# do1.net
KiCad netlist of a schematic drawn in Altium Designer
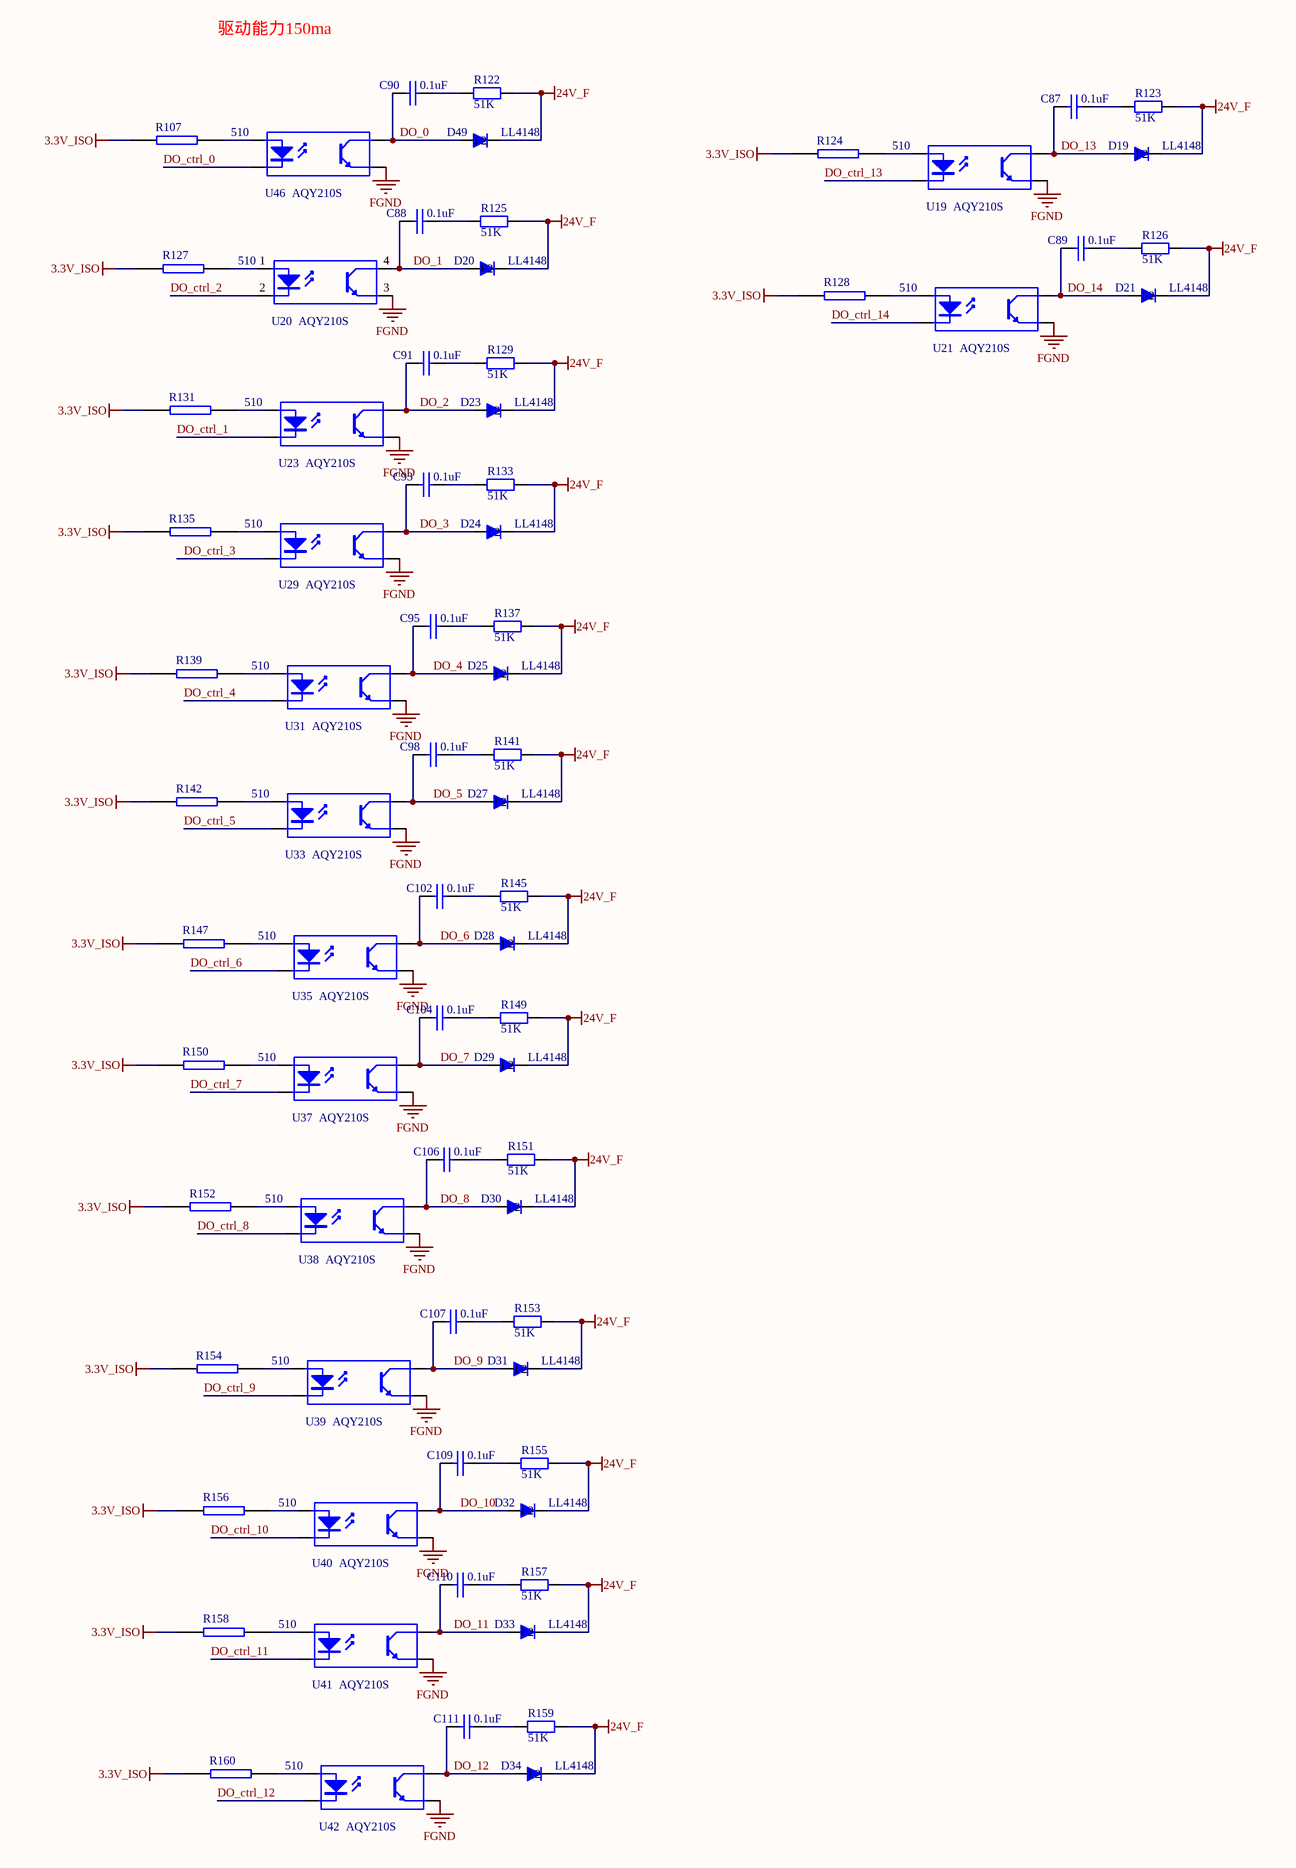
[diagram p0: do1.SchDoc]

(export (version "E")
  (design (tool "Eeschema 10.0.6"))
  (components
    (comp (ref "C87")
      (value "0.1uF")
      (footprint "0603C")
      (description "Capacitor")
      (libsource (lib "*") (part "CAP"))
    )
    (comp (ref "C88")
      (value "0.1uF")
      (footprint "0603C")
      (description "Capacitor")
      (libsource (lib "*") (part "CAP"))
    )
    (comp (ref "C89")
      (value "0.1uF")
      (footprint "0603C")
      (description "Capacitor")
      (libsource (lib "*") (part "CAP"))
    )
    (comp (ref "C90")
      (value "0.1uF")
      (footprint "0603C")
      (description "Capacitor")
      (libsource (lib "*") (part "CAP"))
    )
    (comp (ref "C91")
      (value "0.1uF")
      (footprint "0603C")
      (description "Capacitor")
      (libsource (lib "*") (part "CAP"))
    )
    (comp (ref "C93")
      (value "0.1uF")
      (footprint "0603C")
      (description "Capacitor")
      (libsource (lib "*") (part "CAP"))
    )
    (comp (ref "C95")
      (value "0.1uF")
      (footprint "0603C")
      (description "Capacitor")
      (libsource (lib "*") (part "CAP"))
    )
    (comp (ref "C98")
      (value "0.1uF")
      (footprint "0603C")
      (description "Capacitor")
      (libsource (lib "*") (part "CAP"))
    )
    (comp (ref "C102")
      (value "0.1uF")
      (footprint "0603C")
      (description "Capacitor")
      (libsource (lib "*") (part "CAP"))
    )
    (comp (ref "C104")
      (value "0.1uF")
      (footprint "0603C")
      (description "Capacitor")
      (libsource (lib "*") (part "CAP"))
    )
    (comp (ref "C106")
      (value "0.1uF")
      (footprint "0603C")
      (description "Capacitor")
      (libsource (lib "*") (part "CAP"))
    )
    (comp (ref "C107")
      (value "0.1uF")
      (footprint "0603C")
      (description "Capacitor")
      (libsource (lib "*") (part "CAP"))
    )
    (comp (ref "C109")
      (value "0.1uF")
      (footprint "0603C")
      (description "Capacitor")
      (libsource (lib "*") (part "CAP"))
    )
    (comp (ref "C110")
      (value "0.1uF")
      (footprint "0603C")
      (description "Capacitor")
      (libsource (lib "*") (part "CAP"))
    )
    (comp (ref "C111")
      (value "0.1uF")
      (footprint "0603C")
      (description "Capacitor")
      (libsource (lib "*") (part "CAP"))
    )
    (comp (ref "D19")
      (value "LL4148")
      (footprint "DO-213AB/LL34/MiniMELF")
      (description "VISHAY,LL4148,圆柱体MiniMELF100V/2A,ROHS")
      (libsource (lib "Device2018") (part "LL4148"))
    )
    (comp (ref "D20")
      (value "LL4148")
      (footprint "DO-213AB/LL34/MiniMELF")
      (description "VISHAY,LL4148,圆柱体MiniMELF100V/2A,ROHS")
      (libsource (lib "Device2018") (part "LL4148"))
    )
    (comp (ref "D21")
      (value "LL4148")
      (footprint "DO-213AB/LL34/MiniMELF")
      (description "VISHAY,LL4148,圆柱体MiniMELF100V/2A,ROHS")
      (libsource (lib "Device2018") (part "LL4148"))
    )
    (comp (ref "D23")
      (value "LL4148")
      (footprint "DO-213AB/LL34/MiniMELF")
      (description "VISHAY,LL4148,圆柱体MiniMELF100V/2A,ROHS")
      (libsource (lib "Device2018") (part "LL4148"))
    )
    (comp (ref "D24")
      (value "LL4148")
      (footprint "DO-213AB/LL34/MiniMELF")
      (description "VISHAY,LL4148,圆柱体MiniMELF100V/2A,ROHS")
      (libsource (lib "Device2018") (part "LL4148"))
    )
    (comp (ref "D25")
      (value "LL4148")
      (footprint "DO-213AB/LL34/MiniMELF")
      (description "VISHAY,LL4148,圆柱体MiniMELF100V/2A,ROHS")
      (libsource (lib "Device2018") (part "LL4148"))
    )
    (comp (ref "D27")
      (value "LL4148")
      (footprint "DO-213AB/LL34/MiniMELF")
      (description "VISHAY,LL4148,圆柱体MiniMELF100V/2A,ROHS")
      (libsource (lib "Device2018") (part "LL4148"))
    )
    (comp (ref "D28")
      (value "LL4148")
      (footprint "DO-213AB/LL34/MiniMELF")
      (description "VISHAY,LL4148,圆柱体MiniMELF100V/2A,ROHS")
      (libsource (lib "Device2018") (part "LL4148"))
    )
    (comp (ref "D29")
      (value "LL4148")
      (footprint "DO-213AB/LL34/MiniMELF")
      (description "VISHAY,LL4148,圆柱体MiniMELF100V/2A,ROHS")
      (libsource (lib "Device2018") (part "LL4148"))
    )
    (comp (ref "D30")
      (value "LL4148")
      (footprint "DO-213AB/LL34/MiniMELF")
      (description "VISHAY,LL4148,圆柱体MiniMELF100V/2A,ROHS")
      (libsource (lib "Device2018") (part "LL4148"))
    )
    (comp (ref "D31")
      (value "LL4148")
      (footprint "DO-213AB/LL34/MiniMELF")
      (description "VISHAY,LL4148,圆柱体MiniMELF100V/2A,ROHS")
      (libsource (lib "Device2018") (part "LL4148"))
    )
    (comp (ref "D32")
      (value "LL4148")
      (footprint "DO-213AB/LL34/MiniMELF")
      (description "VISHAY,LL4148,圆柱体MiniMELF100V/2A,ROHS")
      (libsource (lib "Device2018") (part "LL4148"))
    )
    (comp (ref "D33")
      (value "LL4148")
      (footprint "DO-213AB/LL34/MiniMELF")
      (description "VISHAY,LL4148,圆柱体MiniMELF100V/2A,ROHS")
      (libsource (lib "Device2018") (part "LL4148"))
    )
    (comp (ref "D34")
      (value "LL4148")
      (footprint "DO-213AB/LL34/MiniMELF")
      (description "VISHAY,LL4148,圆柱体MiniMELF100V/2A,ROHS")
      (libsource (lib "Device2018") (part "LL4148"))
    )
    (comp (ref "D49")
      (value "LL4148")
      (footprint "DO-213AB/LL34/MiniMELF")
      (description "VISHAY,LL4148,圆柱体MiniMELF100V/2A,ROHS")
      (libsource (lib "Device2018") (part "LL4148"))
    )
    (comp (ref "R107") (value "510") (footprint "0603R") (libsource (lib "*") (part "RES2")))
    (comp (ref "R122") (value "51K") (footprint "0603R") (libsource (lib "MQlibrary") (part "Res0805M")))
    (comp (ref "R123") (value "51K") (footprint "0603R") (libsource (lib "MQlibrary") (part "Res0805M")))
    (comp (ref "R124") (value "510") (footprint "0603R") (libsource (lib "*") (part "RES2")))
    (comp (ref "R125") (value "51K") (footprint "0603R") (libsource (lib "MQlibrary") (part "Res0805M")))
    (comp (ref "R126") (value "51K") (footprint "0603R") (libsource (lib "MQlibrary") (part "Res0805M")))
    (comp (ref "R127") (value "510") (footprint "0603R") (libsource (lib "*") (part "RES2")))
    (comp (ref "R128") (value "510") (footprint "0603R") (libsource (lib "*") (part "RES2")))
    (comp (ref "R129") (value "51K") (footprint "0603R") (libsource (lib "MQlibrary") (part "Res0805M")))
    (comp (ref "R131") (value "510") (footprint "0603R") (libsource (lib "*") (part "RES2")))
    (comp (ref "R133") (value "51K") (footprint "0603R") (libsource (lib "MQlibrary") (part "Res0805M")))
    (comp (ref "R135") (value "510") (footprint "0603R") (libsource (lib "*") (part "RES2")))
    (comp (ref "R137") (value "51K") (footprint "0603R") (libsource (lib "MQlibrary") (part "Res0805M")))
    (comp (ref "R139") (value "510") (footprint "0603R") (libsource (lib "*") (part "RES2")))
    (comp (ref "R141") (value "51K") (footprint "0603R") (libsource (lib "MQlibrary") (part "Res0805M")))
    (comp (ref "R142") (value "510") (footprint "0603R") (libsource (lib "*") (part "RES2")))
    (comp (ref "R145") (value "51K") (footprint "0603R") (libsource (lib "MQlibrary") (part "Res0805M")))
    (comp (ref "R147") (value "510") (footprint "0603R") (libsource (lib "*") (part "RES2")))
    (comp (ref "R149") (value "51K") (footprint "0603R") (libsource (lib "MQlibrary") (part "Res0805M")))
    (comp (ref "R150") (value "510") (footprint "0603R") (libsource (lib "*") (part "RES2")))
    (comp (ref "R151") (value "51K") (footprint "0603R") (libsource (lib "MQlibrary") (part "Res0805M")))
    (comp (ref "R152") (value "510") (footprint "0603R") (libsource (lib "*") (part "RES2")))
    (comp (ref "R153") (value "51K") (footprint "0603R") (libsource (lib "MQlibrary") (part "Res0805M")))
    (comp (ref "R154") (value "510") (footprint "0603R") (libsource (lib "*") (part "RES2")))
    (comp (ref "R155") (value "51K") (footprint "0603R") (libsource (lib "MQlibrary") (part "Res0805M")))
    (comp (ref "R156") (value "510") (footprint "0603R") (libsource (lib "*") (part "RES2")))
    (comp (ref "R157") (value "51K") (footprint "0603R") (libsource (lib "MQlibrary") (part "Res0805M")))
    (comp (ref "R158") (value "510") (footprint "0603R") (libsource (lib "*") (part "RES2")))
    (comp (ref "R159") (value "51K") (footprint "0603R") (libsource (lib "MQlibrary") (part "Res0805M")))
    (comp (ref "R160") (value "510") (footprint "0603R") (libsource (lib "*") (part "RES2")))
    (comp (ref "U19")
      (value "AQY210S")
      (footprint "sop4")
      (description "4-Pin Phototransistor Optocoupler")
      (fields (field (name "PUBLISHER") "Altium Limited"))
      (libsource (lib "Miscellaneous Devices") (part "Optoisolator1"))
    )
    (comp (ref "U20")
      (value "AQY210S")
      (footprint "sop4")
      (description "4-Pin Phototransistor Optocoupler")
      (fields (field (name "PUBLISHER") "Altium Limited"))
      (libsource (lib "") (part "Optoisolator1_1"))
    )
    (comp (ref "U21")
      (value "AQY210S")
      (footprint "sop4")
      (description "4-Pin Phototransistor Optocoupler")
      (fields (field (name "PUBLISHER") "Altium Limited"))
      (libsource (lib "Miscellaneous Devices") (part "Optoisolator1"))
    )
    (comp (ref "U23")
      (value "AQY210S")
      (footprint "sop4")
      (description "4-Pin Phototransistor Optocoupler")
      (fields (field (name "PUBLISHER") "Altium Limited"))
      (libsource (lib "Miscellaneous Devices") (part "Optoisolator1"))
    )
    (comp (ref "U29")
      (value "AQY210S")
      (footprint "sop4")
      (description "4-Pin Phototransistor Optocoupler")
      (fields (field (name "PUBLISHER") "Altium Limited"))
      (libsource (lib "Miscellaneous Devices") (part "Optoisolator1"))
    )
    (comp (ref "U31")
      (value "AQY210S")
      (footprint "sop4")
      (description "4-Pin Phototransistor Optocoupler")
      (fields (field (name "PUBLISHER") "Altium Limited"))
      (libsource (lib "Miscellaneous Devices") (part "Optoisolator1"))
    )
    (comp (ref "U33")
      (value "AQY210S")
      (footprint "sop4")
      (description "4-Pin Phototransistor Optocoupler")
      (fields (field (name "PUBLISHER") "Altium Limited"))
      (libsource (lib "Miscellaneous Devices") (part "Optoisolator1"))
    )
    (comp (ref "U35")
      (value "AQY210S")
      (footprint "sop4")
      (description "4-Pin Phototransistor Optocoupler")
      (fields (field (name "PUBLISHER") "Altium Limited"))
      (libsource (lib "Miscellaneous Devices") (part "Optoisolator1"))
    )
    (comp (ref "U37")
      (value "AQY210S")
      (footprint "sop4")
      (description "4-Pin Phototransistor Optocoupler")
      (fields (field (name "PUBLISHER") "Altium Limited"))
      (libsource (lib "Miscellaneous Devices") (part "Optoisolator1"))
    )
    (comp (ref "U38")
      (value "AQY210S")
      (footprint "sop4")
      (description "4-Pin Phototransistor Optocoupler")
      (fields (field (name "PUBLISHER") "Altium Limited"))
      (libsource (lib "Miscellaneous Devices") (part "Optoisolator1"))
    )
    (comp (ref "U39")
      (value "AQY210S")
      (footprint "sop4")
      (description "4-Pin Phototransistor Optocoupler")
      (fields (field (name "PUBLISHER") "Altium Limited"))
      (libsource (lib "Miscellaneous Devices") (part "Optoisolator1"))
    )
    (comp (ref "U40")
      (value "AQY210S")
      (footprint "sop4")
      (description "4-Pin Phototransistor Optocoupler")
      (fields (field (name "PUBLISHER") "Altium Limited"))
      (libsource (lib "Miscellaneous Devices") (part "Optoisolator1"))
    )
    (comp (ref "U41")
      (value "AQY210S")
      (footprint "sop4")
      (description "4-Pin Phototransistor Optocoupler")
      (fields (field (name "PUBLISHER") "Altium Limited"))
      (libsource (lib "Miscellaneous Devices") (part "Optoisolator1"))
    )
    (comp (ref "U42")
      (value "AQY210S")
      (footprint "sop4")
      (description "4-Pin Phototransistor Optocoupler")
      (fields (field (name "PUBLISHER") "Altium Limited"))
      (libsource (lib "Miscellaneous Devices") (part "Optoisolator1"))
    )
    (comp (ref "U46")
      (value "AQY210S")
      (footprint "sop4")
      (description "4-Pin Phototransistor Optocoupler")
      (fields (field (name "PUBLISHER") "Altium Limited"))
      (libsource (lib "Miscellaneous Devices") (part "Optoisolator1"))
    )
  )
  (nets
    (net (code "1") (name "/DO_0") (class "Default")
      (node (ref "C90") (pin "1") (pinfunction "1_1") (pintype "passive"))
      (node (ref "D49") (pin "1") (pinfunction "2_1") (pintype "passive"))
      (node (ref "U46") (pin "4") (pinfunction "C_4") (pintype "passive"))
    )
    (net (code "2") (name "/DO_1") (class "Default")
      (node (ref "C88") (pin "1") (pinfunction "1_1") (pintype "passive"))
      (node (ref "D20") (pin "1") (pinfunction "2_1") (pintype "passive"))
      (node (ref "U20") (pin "4") (pinfunction "C_4") (pintype "passive"))
    )
    (net (code "3") (name "/DO_2") (class "Default")
      (node (ref "C91") (pin "1") (pinfunction "1_1") (pintype "passive"))
      (node (ref "D23") (pin "1") (pinfunction "2_1") (pintype "passive"))
      (node (ref "U23") (pin "4") (pinfunction "C_4") (pintype "passive"))
    )
    (net (code "4") (name "/DO_3") (class "Default")
      (node (ref "C93") (pin "1") (pinfunction "1_1") (pintype "passive"))
      (node (ref "D24") (pin "1") (pinfunction "2_1") (pintype "passive"))
      (node (ref "U29") (pin "4") (pinfunction "C_4") (pintype "passive"))
    )
    (net (code "5") (name "/DO_4") (class "Default")
      (node (ref "C95") (pin "1") (pinfunction "1_1") (pintype "passive"))
      (node (ref "D25") (pin "1") (pinfunction "2_1") (pintype "passive"))
      (node (ref "U31") (pin "4") (pinfunction "C_4") (pintype "passive"))
    )
    (net (code "6") (name "/DO_5") (class "Default")
      (node (ref "C98") (pin "1") (pinfunction "1_1") (pintype "passive"))
      (node (ref "D27") (pin "1") (pinfunction "2_1") (pintype "passive"))
      (node (ref "U33") (pin "4") (pinfunction "C_4") (pintype "passive"))
    )
    (net (code "7") (name "/DO_6") (class "Default")
      (node (ref "C102") (pin "1") (pinfunction "1_1") (pintype "passive"))
      (node (ref "D28") (pin "1") (pinfunction "2_1") (pintype "passive"))
      (node (ref "U35") (pin "4") (pinfunction "C_4") (pintype "passive"))
    )
    (net (code "8") (name "/DO_7") (class "Default")
      (node (ref "C104") (pin "1") (pinfunction "1_1") (pintype "passive"))
      (node (ref "D29") (pin "1") (pinfunction "2_1") (pintype "passive"))
      (node (ref "U37") (pin "4") (pinfunction "C_4") (pintype "passive"))
    )
    (net (code "9") (name "/DO_8") (class "Default")
      (node (ref "C106") (pin "1") (pinfunction "1_1") (pintype "passive"))
      (node (ref "D30") (pin "1") (pinfunction "2_1") (pintype "passive"))
      (node (ref "U38") (pin "4") (pinfunction "C_4") (pintype "passive"))
    )
    (net (code "10") (name "/DO_9") (class "Default")
      (node (ref "C107") (pin "1") (pinfunction "1_1") (pintype "passive"))
      (node (ref "D31") (pin "1") (pinfunction "2_1") (pintype "passive"))
      (node (ref "U39") (pin "4") (pinfunction "C_4") (pintype "passive"))
    )
    (net (code "11") (name "/DO_10") (class "Default")
      (node (ref "C109") (pin "1") (pinfunction "1_1") (pintype "passive"))
      (node (ref "D32") (pin "1") (pinfunction "2_1") (pintype "passive"))
      (node (ref "U40") (pin "4") (pinfunction "C_4") (pintype "passive"))
    )
    (net (code "12") (name "/DO_11") (class "Default")
      (node (ref "C110") (pin "1") (pinfunction "1_1") (pintype "passive"))
      (node (ref "D33") (pin "1") (pinfunction "2_1") (pintype "passive"))
      (node (ref "U41") (pin "4") (pinfunction "C_4") (pintype "passive"))
    )
    (net (code "13") (name "/DO_12") (class "Default")
      (node (ref "C111") (pin "1") (pinfunction "1_1") (pintype "passive"))
      (node (ref "D34") (pin "1") (pinfunction "2_1") (pintype "passive"))
      (node (ref "U42") (pin "4") (pinfunction "C_4") (pintype "passive"))
    )
    (net (code "14") (name "/DO_13") (class "Default")
      (node (ref "C87") (pin "1") (pinfunction "1_1") (pintype "passive"))
      (node (ref "D19") (pin "1") (pinfunction "2_1") (pintype "passive"))
      (node (ref "U19") (pin "4") (pinfunction "C_4") (pintype "passive"))
    )
    (net (code "15") (name "/DO_14") (class "Default")
      (node (ref "C89") (pin "1") (pinfunction "1_1") (pintype "passive"))
      (node (ref "D21") (pin "1") (pinfunction "2_1") (pintype "passive"))
      (node (ref "U21") (pin "4") (pinfunction "C_4") (pintype "passive"))
    )
    (net (code "16") (name "/DO_ctrl_0") (class "Default")
      (node (ref "U46") (pin "2") (pinfunction "K_2") (pintype "passive"))
    )
    (net (code "17") (name "/DO_ctrl_1") (class "Default")
      (node (ref "U23") (pin "2") (pinfunction "K_2") (pintype "passive"))
    )
    (net (code "18") (name "/DO_ctrl_2") (class "Default")
      (node (ref "U20") (pin "2") (pinfunction "K_2") (pintype "passive"))
    )
    (net (code "19") (name "/DO_ctrl_3") (class "Default")
      (node (ref "U29") (pin "2") (pinfunction "K_2") (pintype "passive"))
    )
    (net (code "20") (name "/DO_ctrl_4") (class "Default")
      (node (ref "U31") (pin "2") (pinfunction "K_2") (pintype "passive"))
    )
    (net (code "21") (name "/DO_ctrl_5") (class "Default")
      (node (ref "U33") (pin "2") (pinfunction "K_2") (pintype "passive"))
    )
    (net (code "22") (name "/DO_ctrl_6") (class "Default")
      (node (ref "U35") (pin "2") (pinfunction "K_2") (pintype "passive"))
    )
    (net (code "23") (name "/DO_ctrl_7") (class "Default")
      (node (ref "U37") (pin "2") (pinfunction "K_2") (pintype "passive"))
    )
    (net (code "24") (name "/DO_ctrl_8") (class "Default")
      (node (ref "U38") (pin "2") (pinfunction "K_2") (pintype "passive"))
    )
    (net (code "25") (name "/DO_ctrl_9") (class "Default")
      (node (ref "U39") (pin "2") (pinfunction "K_2") (pintype "passive"))
    )
    (net (code "26") (name "/DO_ctrl_10") (class "Default")
      (node (ref "U40") (pin "2") (pinfunction "K_2") (pintype "passive"))
    )
    (net (code "27") (name "/DO_ctrl_11") (class "Default")
      (node (ref "U41") (pin "2") (pinfunction "K_2") (pintype "passive"))
    )
    (net (code "28") (name "/DO_ctrl_12") (class "Default")
      (node (ref "U42") (pin "2") (pinfunction "K_2") (pintype "passive"))
    )
    (net (code "29") (name "/DO_ctrl_13") (class "Default")
      (node (ref "U19") (pin "2") (pinfunction "K_2") (pintype "passive"))
    )
    (net (code "30") (name "/DO_ctrl_14") (class "Default")
      (node (ref "U21") (pin "2") (pinfunction "K_2") (pintype "passive"))
    )
    (net (code "31") (name "3.3V_ISO") (class "Default")
      (node (ref "R107") (pin "2") (pinfunction "2_2") (pintype "passive"))
      (node (ref "R124") (pin "2") (pinfunction "2_2") (pintype "passive"))
      (node (ref "R127") (pin "2") (pinfunction "2_2") (pintype "passive"))
      (node (ref "R128") (pin "2") (pinfunction "2_2") (pintype "passive"))
      (node (ref "R131") (pin "2") (pinfunction "2_2") (pintype "passive"))
      (node (ref "R135") (pin "2") (pinfunction "2_2") (pintype "passive"))
      (node (ref "R139") (pin "2") (pinfunction "2_2") (pintype "passive"))
      (node (ref "R142") (pin "2") (pinfunction "2_2") (pintype "passive"))
      (node (ref "R147") (pin "2") (pinfunction "2_2") (pintype "passive"))
      (node (ref "R150") (pin "2") (pinfunction "2_2") (pintype "passive"))
      (node (ref "R152") (pin "2") (pinfunction "2_2") (pintype "passive"))
      (node (ref "R154") (pin "2") (pinfunction "2_2") (pintype "passive"))
      (node (ref "R156") (pin "2") (pinfunction "2_2") (pintype "passive"))
      (node (ref "R158") (pin "2") (pinfunction "2_2") (pintype "passive"))
      (node (ref "R160") (pin "2") (pinfunction "2_2") (pintype "passive"))
    )
    (net (code "32") (name "24V_F") (class "Default")
      (node (ref "D19") (pin "2") (pinfunction "1_2") (pintype "passive"))
      (node (ref "D20") (pin "2") (pinfunction "1_2") (pintype "passive"))
      (node (ref "D21") (pin "2") (pinfunction "1_2") (pintype "passive"))
      (node (ref "D23") (pin "2") (pinfunction "1_2") (pintype "passive"))
      (node (ref "D24") (pin "2") (pinfunction "1_2") (pintype "passive"))
      (node (ref "D25") (pin "2") (pinfunction "1_2") (pintype "passive"))
      (node (ref "D27") (pin "2") (pinfunction "1_2") (pintype "passive"))
      (node (ref "D28") (pin "2") (pinfunction "1_2") (pintype "passive"))
      (node (ref "D29") (pin "2") (pinfunction "1_2") (pintype "passive"))
      (node (ref "D30") (pin "2") (pinfunction "1_2") (pintype "passive"))
      (node (ref "D31") (pin "2") (pinfunction "1_2") (pintype "passive"))
      (node (ref "D32") (pin "2") (pinfunction "1_2") (pintype "passive"))
      (node (ref "D33") (pin "2") (pinfunction "1_2") (pintype "passive"))
      (node (ref "D34") (pin "2") (pinfunction "1_2") (pintype "passive"))
      (node (ref "D49") (pin "2") (pinfunction "1_2") (pintype "passive"))
      (node (ref "R122") (pin "2") (pinfunction "2_2") (pintype "passive"))
      (node (ref "R123") (pin "2") (pinfunction "2_2") (pintype "passive"))
      (node (ref "R125") (pin "2") (pinfunction "2_2") (pintype "passive"))
      (node (ref "R126") (pin "2") (pinfunction "2_2") (pintype "passive"))
      (node (ref "R129") (pin "2") (pinfunction "2_2") (pintype "passive"))
      (node (ref "R133") (pin "2") (pinfunction "2_2") (pintype "passive"))
      (node (ref "R137") (pin "2") (pinfunction "2_2") (pintype "passive"))
      (node (ref "R141") (pin "2") (pinfunction "2_2") (pintype "passive"))
      (node (ref "R145") (pin "2") (pinfunction "2_2") (pintype "passive"))
      (node (ref "R149") (pin "2") (pinfunction "2_2") (pintype "passive"))
      (node (ref "R151") (pin "2") (pinfunction "2_2") (pintype "passive"))
      (node (ref "R153") (pin "2") (pinfunction "2_2") (pintype "passive"))
      (node (ref "R155") (pin "2") (pinfunction "2_2") (pintype "passive"))
      (node (ref "R157") (pin "2") (pinfunction "2_2") (pintype "passive"))
      (node (ref "R159") (pin "2") (pinfunction "2_2") (pintype "passive"))
    )
    (net (code "33") (name "FGND") (class "Default")
      (node (ref "U19") (pin "3") (pinfunction "E_3") (pintype "passive"))
      (node (ref "U20") (pin "3") (pinfunction "E_3") (pintype "passive"))
      (node (ref "U21") (pin "3") (pinfunction "E_3") (pintype "passive"))
      (node (ref "U23") (pin "3") (pinfunction "E_3") (pintype "passive"))
      (node (ref "U29") (pin "3") (pinfunction "E_3") (pintype "passive"))
      (node (ref "U31") (pin "3") (pinfunction "E_3") (pintype "passive"))
      (node (ref "U33") (pin "3") (pinfunction "E_3") (pintype "passive"))
      (node (ref "U35") (pin "3") (pinfunction "E_3") (pintype "passive"))
      (node (ref "U37") (pin "3") (pinfunction "E_3") (pintype "passive"))
      (node (ref "U38") (pin "3") (pinfunction "E_3") (pintype "passive"))
      (node (ref "U39") (pin "3") (pinfunction "E_3") (pintype "passive"))
      (node (ref "U40") (pin "3") (pinfunction "E_3") (pintype "passive"))
      (node (ref "U41") (pin "3") (pinfunction "E_3") (pintype "passive"))
      (node (ref "U42") (pin "3") (pinfunction "E_3") (pintype "passive"))
      (node (ref "U46") (pin "3") (pinfunction "E_3") (pintype "passive"))
    )
    (net (code "34") (name "Net-(C87-Pad2)") (class "Default")
      (node (ref "C87") (pin "2") (pinfunction "2_2") (pintype "passive"))
      (node (ref "R123") (pin "1") (pinfunction "1_1") (pintype "passive"))
    )
    (net (code "35") (name "Net-(C88-Pad2)") (class "Default")
      (node (ref "C88") (pin "2") (pinfunction "2_2") (pintype "passive"))
      (node (ref "R125") (pin "1") (pinfunction "1_1") (pintype "passive"))
    )
    (net (code "36") (name "Net-(C89-Pad2)") (class "Default")
      (node (ref "C89") (pin "2") (pinfunction "2_2") (pintype "passive"))
      (node (ref "R126") (pin "1") (pinfunction "1_1") (pintype "passive"))
    )
    (net (code "37") (name "Net-(C90-Pad2)") (class "Default")
      (node (ref "C90") (pin "2") (pinfunction "2_2") (pintype "passive"))
      (node (ref "R122") (pin "1") (pinfunction "1_1") (pintype "passive"))
    )
    (net (code "38") (name "Net-(C91-Pad2)") (class "Default")
      (node (ref "C91") (pin "2") (pinfunction "2_2") (pintype "passive"))
      (node (ref "R129") (pin "1") (pinfunction "1_1") (pintype "passive"))
    )
    (net (code "39") (name "Net-(C93-Pad2)") (class "Default")
      (node (ref "C93") (pin "2") (pinfunction "2_2") (pintype "passive"))
      (node (ref "R133") (pin "1") (pinfunction "1_1") (pintype "passive"))
    )
    (net (code "40") (name "Net-(C95-Pad2)") (class "Default")
      (node (ref "C95") (pin "2") (pinfunction "2_2") (pintype "passive"))
      (node (ref "R137") (pin "1") (pinfunction "1_1") (pintype "passive"))
    )
    (net (code "41") (name "Net-(C98-Pad2)") (class "Default")
      (node (ref "C98") (pin "2") (pinfunction "2_2") (pintype "passive"))
      (node (ref "R141") (pin "1") (pinfunction "1_1") (pintype "passive"))
    )
    (net (code "42") (name "Net-(C102-Pad2)") (class "Default")
      (node (ref "C102") (pin "2") (pinfunction "2_2") (pintype "passive"))
      (node (ref "R145") (pin "1") (pinfunction "1_1") (pintype "passive"))
    )
    (net (code "43") (name "Net-(C104-Pad2)") (class "Default")
      (node (ref "C104") (pin "2") (pinfunction "2_2") (pintype "passive"))
      (node (ref "R149") (pin "1") (pinfunction "1_1") (pintype "passive"))
    )
    (net (code "44") (name "Net-(C106-Pad2)") (class "Default")
      (node (ref "C106") (pin "2") (pinfunction "2_2") (pintype "passive"))
      (node (ref "R151") (pin "1") (pinfunction "1_1") (pintype "passive"))
    )
    (net (code "45") (name "Net-(C107-Pad2)") (class "Default")
      (node (ref "C107") (pin "2") (pinfunction "2_2") (pintype "passive"))
      (node (ref "R153") (pin "1") (pinfunction "1_1") (pintype "passive"))
    )
    (net (code "46") (name "Net-(C109-Pad2)") (class "Default")
      (node (ref "C109") (pin "2") (pinfunction "2_2") (pintype "passive"))
      (node (ref "R155") (pin "1") (pinfunction "1_1") (pintype "passive"))
    )
    (net (code "47") (name "Net-(C110-Pad2)") (class "Default")
      (node (ref "C110") (pin "2") (pinfunction "2_2") (pintype "passive"))
      (node (ref "R157") (pin "1") (pinfunction "1_1") (pintype "passive"))
    )
    (net (code "48") (name "Net-(C111-Pad2)") (class "Default")
      (node (ref "C111") (pin "2") (pinfunction "2_2") (pintype "passive"))
      (node (ref "R159") (pin "1") (pinfunction "1_1") (pintype "passive"))
    )
    (net (code "49") (name "Net-(U19-A)") (class "Default")
      (node (ref "R124") (pin "1") (pinfunction "1_1") (pintype "passive"))
      (node (ref "U19") (pin "1") (pinfunction "A_1") (pintype "passive"))
    )
    (net (code "50") (name "Net-(U20-A)") (class "Default")
      (node (ref "R127") (pin "1") (pinfunction "1_1") (pintype "passive"))
      (node (ref "U20") (pin "1") (pinfunction "A_1") (pintype "passive"))
    )
    (net (code "51") (name "Net-(U21-A)") (class "Default")
      (node (ref "R128") (pin "1") (pinfunction "1_1") (pintype "passive"))
      (node (ref "U21") (pin "1") (pinfunction "A_1") (pintype "passive"))
    )
    (net (code "52") (name "Net-(U23-A)") (class "Default")
      (node (ref "R131") (pin "1") (pinfunction "1_1") (pintype "passive"))
      (node (ref "U23") (pin "1") (pinfunction "A_1") (pintype "passive"))
    )
    (net (code "53") (name "Net-(U29-A)") (class "Default")
      (node (ref "R135") (pin "1") (pinfunction "1_1") (pintype "passive"))
      (node (ref "U29") (pin "1") (pinfunction "A_1") (pintype "passive"))
    )
    (net (code "54") (name "Net-(U31-A)") (class "Default")
      (node (ref "R139") (pin "1") (pinfunction "1_1") (pintype "passive"))
      (node (ref "U31") (pin "1") (pinfunction "A_1") (pintype "passive"))
    )
    (net (code "55") (name "Net-(U33-A)") (class "Default")
      (node (ref "R142") (pin "1") (pinfunction "1_1") (pintype "passive"))
      (node (ref "U33") (pin "1") (pinfunction "A_1") (pintype "passive"))
    )
    (net (code "56") (name "Net-(U35-A)") (class "Default")
      (node (ref "R147") (pin "1") (pinfunction "1_1") (pintype "passive"))
      (node (ref "U35") (pin "1") (pinfunction "A_1") (pintype "passive"))
    )
    (net (code "57") (name "Net-(U37-A)") (class "Default")
      (node (ref "R150") (pin "1") (pinfunction "1_1") (pintype "passive"))
      (node (ref "U37") (pin "1") (pinfunction "A_1") (pintype "passive"))
    )
    (net (code "58") (name "Net-(U38-A)") (class "Default")
      (node (ref "R152") (pin "1") (pinfunction "1_1") (pintype "passive"))
      (node (ref "U38") (pin "1") (pinfunction "A_1") (pintype "passive"))
    )
    (net (code "59") (name "Net-(U39-A)") (class "Default")
      (node (ref "R154") (pin "1") (pinfunction "1_1") (pintype "passive"))
      (node (ref "U39") (pin "1") (pinfunction "A_1") (pintype "passive"))
    )
    (net (code "60") (name "Net-(U40-A)") (class "Default")
      (node (ref "R156") (pin "1") (pinfunction "1_1") (pintype "passive"))
      (node (ref "U40") (pin "1") (pinfunction "A_1") (pintype "passive"))
    )
    (net (code "61") (name "Net-(U41-A)") (class "Default")
      (node (ref "R158") (pin "1") (pinfunction "1_1") (pintype "passive"))
      (node (ref "U41") (pin "1") (pinfunction "A_1") (pintype "passive"))
    )
    (net (code "62") (name "Net-(U42-A)") (class "Default")
      (node (ref "R160") (pin "1") (pinfunction "1_1") (pintype "passive"))
      (node (ref "U42") (pin "1") (pinfunction "A_1") (pintype "passive"))
    )
    (net (code "63") (name "Net-(U46-A)") (class "Default")
      (node (ref "R107") (pin "1") (pinfunction "1_1") (pintype "passive"))
      (node (ref "U46") (pin "1") (pinfunction "A_1") (pintype "passive"))
    )
  )
)
